# interface_spellman_detector.net
KiCad netlist of a schematic drawn in EAGLE
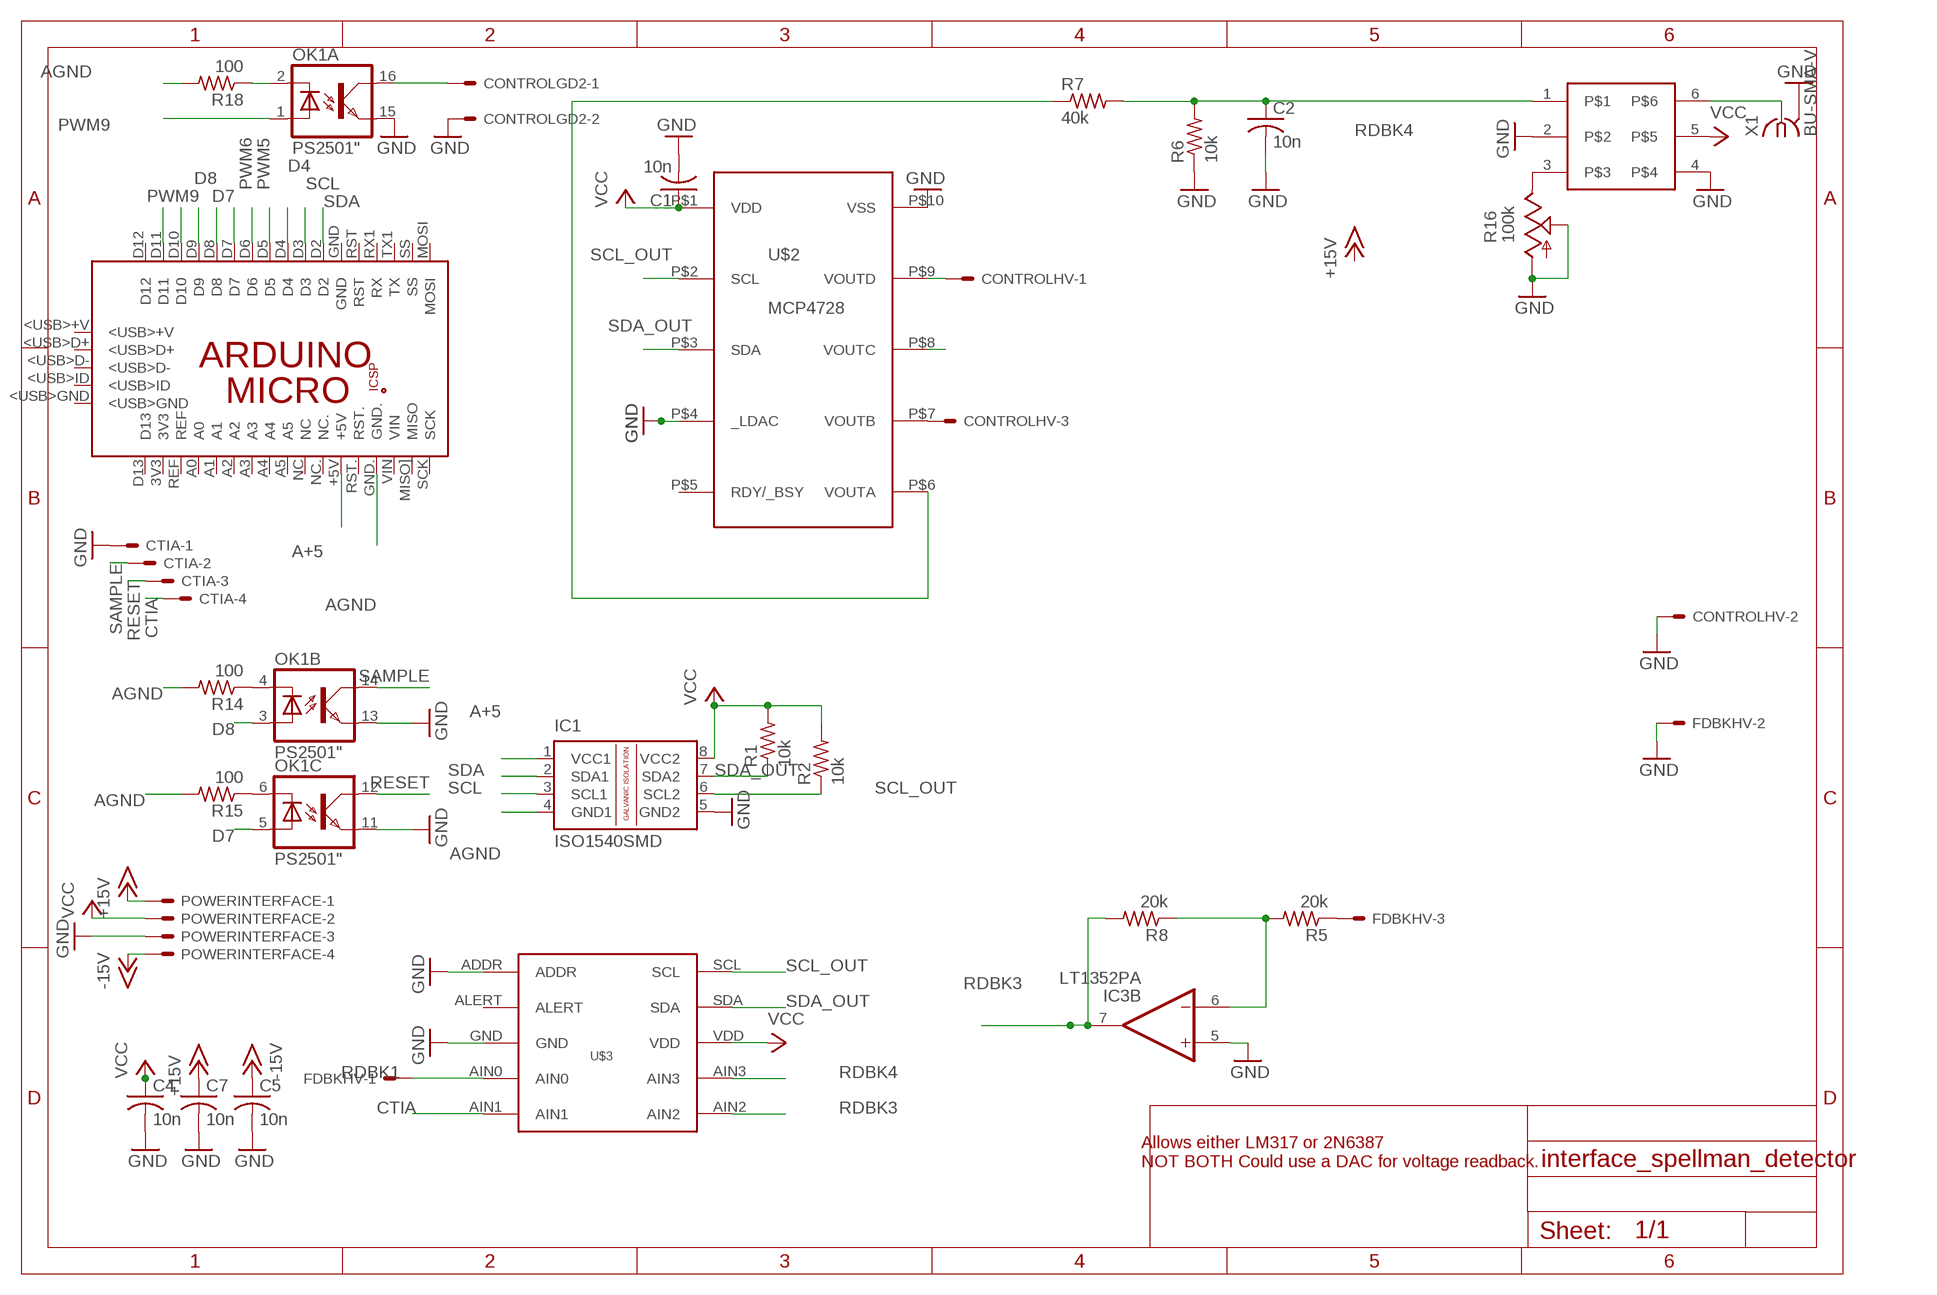
[diagram p0: schematic, sheet 1]

(export (version "E")
  (design (tool "Eeschema 10.0.6"))
  (components
    (comp (ref "C1")
      (value "10n")
      (footprint "eagle-import:C0805K")
      (libsource (lib "eagle-import") (part "C-USC0805K"))
    )
    (comp (ref "C2")
      (value "10n")
      (footprint "eagle-import:C0805K")
      (libsource (lib "eagle-import") (part "resistor_C-USC0805K"))
    )
    (comp (ref "C4")
      (value "10n")
      (footprint "eagle-import:C0805K")
      (libsource (lib "eagle-import") (part "resistor_C-USC0805K"))
    )
    (comp (ref "C5")
      (value "10n")
      (footprint "eagle-import:C0805K")
      (libsource (lib "eagle-import") (part "resistor_C-USC0805K"))
    )
    (comp (ref "C7")
      (value "10n")
      (footprint "eagle-import:C0805K")
      (libsource (lib "eagle-import") (part "resistor_C-USC0805K"))
    )
    (comp (ref "CONTROLGD2")
      (value "KK-156-2")
      (footprint "eagle-import:KK-156-2")
      (libsource (lib "eagle-import") (part "KK-156-2"))
    )
    (comp (ref "CONTROLHV")
      (value "KK-156-3")
      (footprint "eagle-import:KK-156-3")
      (libsource (lib "eagle-import") (part "KK-156-3"))
    )
    (comp (ref "CTIA")
      (value "KK-156-4")
      (footprint "eagle-import:KK-156-4")
      (libsource (lib "eagle-import") (part "KK-156-4"))
    )
    (comp (ref "FDBKHV")
      (value "KK-156-3")
      (footprint "eagle-import:KK-156-3")
      (libsource (lib "eagle-import") (part "KK-156-3"))
    )
    (comp (ref "IC1")
      (value "ISO1540SMD")
      (footprint "eagle-import:SOIC8")
      (libsource (lib "eagle-import") (part "ISO1540SMD"))
    )
    (comp (ref "IC3")
      (value "LT1352PA")
      (footprint "eagle-import:DIL08")
      (libsource (lib "eagle-import") (part "LT1352PA"))
    )
    (comp (ref "OK1")
      (value "PS2501\"")
      (footprint "eagle-import:DIL16")
      (libsource (lib "eagle-import") (part "PS2501{dblquote}"))
    )
    (comp (ref "PCB1")
      (value "ARDUINO_MICRO")
      (footprint "eagle-import:ARDUINO_MICRO")
      (libsource (lib "eagle-import") (part "ARDUINO_MICRO"))
    )
    (comp (ref "POWERINTERFACE")
      (value "KK-156-4")
      (footprint "eagle-import:KK-156-4")
      (libsource (lib "eagle-import") (part "KK-156-4"))
    )
    (comp (ref "R1")
      (value "10k")
      (footprint "eagle-import:R0805")
      (libsource (lib "eagle-import") (part "resistor_R-US_R0805"))
    )
    (comp (ref "R2")
      (value "10k")
      (footprint "eagle-import:R0805")
      (libsource (lib "eagle-import") (part "resistor_R-US_R0805"))
    )
    (comp (ref "R5")
      (value "20k")
      (footprint "eagle-import:R0805")
      (libsource (lib "eagle-import") (part "resistor_R-US_R0805"))
    )
    (comp (ref "R6")
      (value "10k")
      (footprint "eagle-import:R0805")
      (libsource (lib "eagle-import") (part "resistor_R-US_R0805"))
    )
    (comp (ref "R7")
      (value "40k")
      (footprint "eagle-import:R0805")
      (libsource (lib "eagle-import") (part "resistor_R-US_R0805"))
    )
    (comp (ref "R8")
      (value "20k")
      (footprint "eagle-import:R0805")
      (libsource (lib "eagle-import") (part "resistor_R-US_R0805"))
    )
    (comp (ref "R14")
      (value "100")
      (footprint "eagle-import:R0805")
      (libsource (lib "eagle-import") (part "R-US_R0805"))
    )
    (comp (ref "R15")
      (value "100")
      (footprint "eagle-import:R0805")
      (libsource (lib "eagle-import") (part "R-US_R0805"))
    )
    (comp (ref "R16")
      (value "100k")
      (footprint "eagle-import:B64Y")
      (libsource (lib "eagle-import") (part "TRIM_US-B64Y"))
    )
    (comp (ref "R18")
      (value "100")
      (footprint "eagle-import:R0805")
      (libsource (lib "eagle-import") (part "R-US_R0805"))
    )
    (comp (ref "U$1")
      (value "LTC6992SMD")
      (footprint "eagle-import:SOT23-6")
      (libsource (lib "eagle-import") (part "LTC6992SMD"))
    )
    (comp (ref "U$2")
      (value "MCP4728")
      (footprint "eagle-import:MSOP-10")
      (libsource (lib "eagle-import") (part "MCP4728"))
    )
    (comp (ref "U$3")
      (value "ADS1015")
      (footprint "eagle-import:VSOP-10")
      (libsource (lib "eagle-import") (part "ADS1015"))
    )
    (comp (ref "X1")
      (value "BU-SMA-V")
      (footprint "eagle-import:BU-SMA-V")
      (libsource (lib "eagle-import") (part "BU-SMA-V"))
    )
  )
  (nets
    (net (code "1") (name "+15V") (class "Default")
      (node (ref "C7") (pin "1") (pinfunction "1_1") (pintype "passive"))
      (node (ref "POWERINTERFACE") (pin "1") (pinfunction "S_1") (pintype "passive"))
    )
    (net (code "2") (name "-15V") (class "Default")
      (node (ref "C5") (pin "1") (pinfunction "1_1") (pintype "passive"))
      (node (ref "POWERINTERFACE") (pin "4") (pinfunction "S_4") (pintype "passive"))
    )
    (net (code "3") (name "/A+5") (class "Default")
      (node (ref "IC1") (pin "1") (pinfunction "VCC1_1") (pintype "input"))
      (node (ref "PCB1") (pin "+5V") (pinfunction "+5V_+5V") (pintype "bidirectional"))
    )
    (net (code "4") (name "/AGND") (class "Default")
      (node (ref "IC1") (pin "4") (pinfunction "GND1_4") (pintype "input"))
      (node (ref "PCB1") (pin "GND.") (pinfunction "GND._GND.") (pintype "bidirectional"))
      (node (ref "R14") (pin "2") (pinfunction "2_2") (pintype "passive"))
      (node (ref "R15") (pin "2") (pinfunction "2_2") (pintype "passive"))
      (node (ref "R18") (pin "2") (pinfunction "2_2") (pintype "passive"))
    )
    (net (code "5") (name "/CTIA") (class "Default")
      (node (ref "CTIA") (pin "4") (pinfunction "S_4") (pintype "passive"))
      (node (ref "U$3") (pin "AIN1") (pinfunction "AIN1_AIN1") (pintype "bidirectional"))
    )
    (net (code "6") (name "/D4") (class "Default")
      (node (ref "PCB1") (pin "D4") (pinfunction "D4_D4") (pintype "bidirectional"))
    )
    (net (code "7") (name "/D7") (class "Default")
      (node (ref "OK1") (pin "5") (pinfunction "A_5") (pintype "passive"))
      (node (ref "PCB1") (pin "D7") (pinfunction "D7_D7") (pintype "bidirectional"))
    )
    (net (code "8") (name "/D8") (class "Default")
      (node (ref "OK1") (pin "3") (pinfunction "A_3") (pintype "passive"))
      (node (ref "PCB1") (pin "D8") (pinfunction "D8_D8") (pintype "bidirectional"))
    )
    (net (code "9") (name "/PWM5") (class "Default")
      (node (ref "PCB1") (pin "D5") (pinfunction "D5_D5") (pintype "bidirectional"))
    )
    (net (code "10") (name "/PWM6") (class "Default")
      (node (ref "PCB1") (pin "D6") (pinfunction "D6_D6") (pintype "bidirectional"))
    )
    (net (code "11") (name "/PWM9") (class "Default")
      (node (ref "OK1") (pin "1") (pinfunction "A_1") (pintype "passive"))
      (node (ref "PCB1") (pin "D9") (pinfunction "D9_D9") (pintype "bidirectional"))
    )
    (net (code "12") (name "/RDBK1") (class "Default")
      (node (ref "FDBKHV") (pin "1") (pinfunction "S_1") (pintype "passive"))
      (node (ref "U$3") (pin "AIN0") (pinfunction "AIN0_AIN0") (pintype "bidirectional"))
    )
    (net (code "13") (name "/RDBK3") (class "Default")
      (node (ref "IC3") (pin "7") (pinfunction "OUT_7") (pintype "output"))
      (node (ref "R8") (pin "2") (pinfunction "2_2") (pintype "passive"))
      (node (ref "U$3") (pin "AIN2") (pinfunction "AIN2_AIN2") (pintype "bidirectional"))
    )
    (net (code "14") (name "/RDBK4") (class "Default")
      (node (ref "C2") (pin "1") (pinfunction "1_1") (pintype "passive"))
      (node (ref "R6") (pin "2") (pinfunction "2_2") (pintype "passive"))
      (node (ref "R7") (pin "2") (pinfunction "2_2") (pintype "passive"))
      (node (ref "U$1") (pin "1") (pinfunction "P$1_1") (pintype "bidirectional"))
      (node (ref "U$3") (pin "AIN3") (pinfunction "AIN3_AIN3") (pintype "bidirectional"))
    )
    (net (code "15") (name "/RESET") (class "Default")
      (node (ref "CTIA") (pin "3") (pinfunction "S_3") (pintype "passive"))
      (node (ref "OK1") (pin "12") (pinfunction "COL_12") (pintype "passive"))
    )
    (net (code "16") (name "/SAMPLE") (class "Default")
      (node (ref "CTIA") (pin "2") (pinfunction "S_2") (pintype "passive"))
      (node (ref "OK1") (pin "14") (pinfunction "COL_14") (pintype "passive"))
    )
    (net (code "17") (name "/SCL") (class "Default")
      (node (ref "IC1") (pin "3") (pinfunction "SCL1_3") (pintype "input"))
      (node (ref "PCB1") (pin "D3") (pinfunction "D3_D3") (pintype "bidirectional"))
    )
    (net (code "18") (name "/SCL_OUT") (class "Default")
      (node (ref "IC1") (pin "6") (pinfunction "SCL2_6") (pintype "input"))
      (node (ref "R2") (pin "1") (pinfunction "1_1") (pintype "passive"))
      (node (ref "U$2") (pin "P$2") (pinfunction "SCL_P$2") (pintype "bidirectional"))
      (node (ref "U$3") (pin "SCL") (pinfunction "SCL_SCL") (pintype "bidirectional"))
    )
    (net (code "19") (name "/SDA") (class "Default")
      (node (ref "IC1") (pin "2") (pinfunction "SDA1_2") (pintype "input"))
      (node (ref "PCB1") (pin "D2") (pinfunction "D2_D2") (pintype "bidirectional"))
    )
    (net (code "20") (name "/SDA_OUT") (class "Default")
      (node (ref "IC1") (pin "7") (pinfunction "SDA2_7") (pintype "input"))
      (node (ref "R1") (pin "1") (pinfunction "1_1") (pintype "passive"))
      (node (ref "U$2") (pin "P$3") (pinfunction "SDA_P$3") (pintype "bidirectional"))
      (node (ref "U$3") (pin "SDA") (pinfunction "SDA_SDA") (pintype "bidirectional"))
    )
    (net (code "21") (name "GND") (class "Default")
      (node (ref "C1") (pin "2") (pinfunction "2_2") (pintype "passive"))
      (node (ref "C2") (pin "2") (pinfunction "2_2") (pintype "passive"))
      (node (ref "C4") (pin "2") (pinfunction "2_2") (pintype "passive"))
      (node (ref "C5") (pin "2") (pinfunction "2_2") (pintype "passive"))
      (node (ref "C7") (pin "2") (pinfunction "2_2") (pintype "passive"))
      (node (ref "CONTROLGD2") (pin "2") (pinfunction "S_2") (pintype "passive"))
      (node (ref "CONTROLHV") (pin "2") (pinfunction "S_2") (pintype "passive"))
      (node (ref "CTIA") (pin "1") (pinfunction "S_1") (pintype "passive"))
      (node (ref "FDBKHV") (pin "2") (pinfunction "S_2") (pintype "passive"))
      (node (ref "IC1") (pin "5") (pinfunction "GND2_5") (pintype "input"))
      (node (ref "IC3") (pin "5") (pinfunction "+IN_5") (pintype "input"))
      (node (ref "OK1") (pin "11") (pinfunction "EMI_11") (pintype "passive"))
      (node (ref "OK1") (pin "13") (pinfunction "EMI_13") (pintype "passive"))
      (node (ref "OK1") (pin "15") (pinfunction "EMI_15") (pintype "passive"))
      (node (ref "POWERINTERFACE") (pin "3") (pinfunction "S_3") (pintype "passive"))
      (node (ref "R16") (pin "A") (pinfunction "A_A") (pintype "passive"))
      (node (ref "R16") (pin "S") (pinfunction "S_S") (pintype "passive"))
      (node (ref "R6") (pin "1") (pinfunction "1_1") (pintype "passive"))
      (node (ref "U$1") (pin "2") (pinfunction "P$2_2") (pintype "bidirectional"))
      (node (ref "U$1") (pin "4") (pinfunction "P$4_4") (pintype "bidirectional"))
      (node (ref "U$2") (pin "P$10") (pinfunction "VSS_P$10") (pintype "bidirectional"))
      (node (ref "U$2") (pin "P$4") (pinfunction "_LDAC_P$4") (pintype "bidirectional"))
      (node (ref "U$3") (pin "ADDR") (pinfunction "ADDR_ADDR") (pintype "bidirectional"))
      (node (ref "U$3") (pin "GND") (pinfunction "GND_GND") (pintype "bidirectional"))
      (node (ref "X1") (pin "2") (pinfunction "2_2") (pintype "passive"))
      (node (ref "X1") (pin "3") (pinfunction "2_3") (pintype "passive"))
      (node (ref "X1") (pin "4") (pinfunction "2_4") (pintype "passive"))
      (node (ref "X1") (pin "5") (pinfunction "2_5") (pintype "passive"))
    )
    (net (code "22") (name "Net-(CONTROLGD2A-S)") (class "Default")
      (node (ref "CONTROLGD2") (pin "1") (pinfunction "S_1") (pintype "passive"))
      (node (ref "OK1") (pin "16") (pinfunction "COL_16") (pintype "passive"))
    )
    (net (code "23") (name "Net-(CONTROLHVA-S)") (class "Default")
      (node (ref "CONTROLHV") (pin "1") (pinfunction "S_1") (pintype "passive"))
      (node (ref "U$2") (pin "P$9") (pinfunction "VOUTD_P$9") (pintype "bidirectional"))
    )
    (net (code "24") (name "Net-(CONTROLHVC-S)") (class "Default")
      (node (ref "CONTROLHV") (pin "3") (pinfunction "S_3") (pintype "passive"))
      (node (ref "U$2") (pin "P$7") (pinfunction "VOUTB_P$7") (pintype "bidirectional"))
    )
    (net (code "25") (name "Net-(FDBKHVC-S)") (class "Default")
      (node (ref "FDBKHV") (pin "3") (pinfunction "S_3") (pintype "passive"))
      (node (ref "R5") (pin "1") (pinfunction "1_1") (pintype "passive"))
    )
    (net (code "26") (name "Net-(IC3B--IN)") (class "Default")
      (node (ref "IC3") (pin "6") (pinfunction "-IN_6") (pintype "input"))
      (node (ref "R5") (pin "2") (pinfunction "2_2") (pintype "passive"))
      (node (ref "R8") (pin "1") (pinfunction "1_1") (pintype "passive"))
    )
    (net (code "27") (name "Net-(OK1A-C)") (class "Default")
      (node (ref "OK1") (pin "2") (pinfunction "C_2") (pintype "passive"))
      (node (ref "R18") (pin "1") (pinfunction "1_1") (pintype "passive"))
    )
    (net (code "28") (name "Net-(OK1B-C)") (class "Default")
      (node (ref "OK1") (pin "4") (pinfunction "C_4") (pintype "passive"))
      (node (ref "R14") (pin "1") (pinfunction "1_1") (pintype "passive"))
    )
    (net (code "29") (name "Net-(OK1C-C)") (class "Default")
      (node (ref "OK1") (pin "6") (pinfunction "C_6") (pintype "passive"))
      (node (ref "R15") (pin "1") (pinfunction "1_1") (pintype "passive"))
    )
    (net (code "30") (name "Net-(U$1-P$3)") (class "Default")
      (node (ref "R16") (pin "E") (pinfunction "E_E") (pintype "passive"))
      (node (ref "U$1") (pin "3") (pinfunction "P$3_3") (pintype "bidirectional"))
    )
    (net (code "31") (name "Net-(U$1-P$6)") (class "Default")
      (node (ref "U$1") (pin "6") (pinfunction "P$6_6") (pintype "bidirectional"))
      (node (ref "X1") (pin "1") (pinfunction "1_1") (pintype "passive"))
    )
    (net (code "32") (name "Net-(U$2-VOUTA)") (class "Default")
      (node (ref "R7") (pin "1") (pinfunction "1_1") (pintype "passive"))
      (node (ref "U$2") (pin "P$6") (pinfunction "VOUTA_P$6") (pintype "bidirectional"))
    )
    (net (code "33") (name "VCC") (class "Default")
      (node (ref "C1") (pin "1") (pinfunction "1_1") (pintype "passive"))
      (node (ref "C4") (pin "1") (pinfunction "1_1") (pintype "passive"))
      (node (ref "IC1") (pin "8") (pinfunction "VCC2_8") (pintype "input"))
      (node (ref "POWERINTERFACE") (pin "2") (pinfunction "S_2") (pintype "passive"))
      (node (ref "R1") (pin "2") (pinfunction "2_2") (pintype "passive"))
      (node (ref "R2") (pin "2") (pinfunction "2_2") (pintype "passive"))
      (node (ref "U$1") (pin "5") (pinfunction "P$5_5") (pintype "bidirectional"))
      (node (ref "U$2") (pin "P$1") (pinfunction "VDD_P$1") (pintype "bidirectional"))
      (node (ref "U$3") (pin "VDD") (pinfunction "VDD_VDD") (pintype "bidirectional"))
    )
    (net (code "34") (name "unconnected-(PCB1-MISO-PadMISO])") (class "Default")
      (node (ref "PCB1") (pin "MISO]") (pinfunction "MISO_MISO]") (pintype "bidirectional"))
    )
    (net (code "35") (name "unconnected-(PCB1-Pad3V3)") (class "Default")
      (node (ref "PCB1") (pin "3V3") (pinfunction "3V3_3V3") (pintype "bidirectional"))
    )
    (net (code "36") (name "unconnected-(PCB1-Pad5V)") (class "Default")
      (node (ref "PCB1") (pin "5V") (pinfunction "5V_5V") (pintype "bidirectional"))
    )
    (net (code "37") (name "unconnected-(PCB1-Pad<USB>+V)") (class "Default")
      (node (ref "PCB1") (pin "<USB>+V") (pinfunction "<USB>+V_<USB>+V") (pintype "bidirectional"))
    )
    (net (code "38") (name "unconnected-(PCB1-Pad<USB>D+)") (class "Default")
      (node (ref "PCB1") (pin "<USB>D+") (pinfunction "<USB>D+_<USB>D+") (pintype "bidirectional"))
    )
    (net (code "39") (name "unconnected-(PCB1-Pad<USB>D-)") (class "Default")
      (node (ref "PCB1") (pin "<USB>D-") (pinfunction "<USB>D-_<USB>D-") (pintype "bidirectional"))
    )
    (net (code "40") (name "unconnected-(PCB1-Pad<USB>GND)") (class "Default")
      (node (ref "PCB1") (pin "<USB>GND") (pinfunction "<USB>GND_<USB>GND") (pintype "bidirectional"))
    )
    (net (code "41") (name "unconnected-(PCB1-Pad<USB>ID)") (class "Default")
      (node (ref "PCB1") (pin "<USB>ID") (pinfunction "<USB>ID_<USB>ID") (pintype "bidirectional"))
    )
    (net (code "42") (name "unconnected-(PCB1-PadA0)") (class "Default")
      (node (ref "PCB1") (pin "A0") (pinfunction "A0_A0") (pintype "bidirectional"))
    )
    (net (code "43") (name "unconnected-(PCB1-PadA1)") (class "Default")
      (node (ref "PCB1") (pin "A1") (pinfunction "A1_A1") (pintype "bidirectional"))
    )
    (net (code "44") (name "unconnected-(PCB1-PadA2)") (class "Default")
      (node (ref "PCB1") (pin "A2") (pinfunction "A2_A2") (pintype "bidirectional"))
    )
    (net (code "45") (name "unconnected-(PCB1-PadA3)") (class "Default")
      (node (ref "PCB1") (pin "A3") (pinfunction "A3_A3") (pintype "bidirectional"))
    )
    (net (code "46") (name "unconnected-(PCB1-PadA4)") (class "Default")
      (node (ref "PCB1") (pin "A4") (pinfunction "A4_A4") (pintype "bidirectional"))
    )
    (net (code "47") (name "unconnected-(PCB1-PadA5)") (class "Default")
      (node (ref "PCB1") (pin "A5") (pinfunction "A5_A5") (pintype "bidirectional"))
    )
    (net (code "48") (name "unconnected-(PCB1-PadD10)") (class "Default")
      (node (ref "PCB1") (pin "D10") (pinfunction "D10_D10") (pintype "bidirectional"))
    )
    (net (code "49") (name "unconnected-(PCB1-PadD11)") (class "Default")
      (node (ref "PCB1") (pin "D11") (pinfunction "D11_D11") (pintype "bidirectional"))
    )
    (net (code "50") (name "unconnected-(PCB1-PadD12)") (class "Default")
      (node (ref "PCB1") (pin "D12") (pinfunction "D12_D12") (pintype "bidirectional"))
    )
    (net (code "51") (name "unconnected-(PCB1-PadD13)") (class "Default")
      (node (ref "PCB1") (pin "D13") (pinfunction "D13_D13") (pintype "bidirectional"))
    )
    (net (code "52") (name "unconnected-(PCB1-PadGND)") (class "Default")
      (node (ref "PCB1") (pin "GND") (pinfunction "GND_GND") (pintype "bidirectional"))
    )
    (net (code "53") (name "unconnected-(PCB1-PadGND_)") (class "Default")
      (node (ref "PCB1") (pin "GND_") (pinfunction "GND__GND_") (pintype "bidirectional"))
    )
    (net (code "54") (name "unconnected-(PCB1-PadMISO.)") (class "Default")
      (node (ref "PCB1") (pin "MISO.") (pinfunction "MISO._MISO.") (pintype "bidirectional"))
    )
    (net (code "55") (name "unconnected-(PCB1-PadMOSI)") (class "Default")
      (node (ref "PCB1") (pin "MOSI") (pinfunction "MOSI_MOSI") (pintype "bidirectional"))
    )
    (net (code "56") (name "unconnected-(PCB1-PadMOSI.)") (class "Default")
      (node (ref "PCB1") (pin "MOSI.") (pinfunction "MOSI._MOSI.") (pintype "bidirectional"))
    )
    (net (code "57") (name "unconnected-(PCB1-PadNC)") (class "Default")
      (node (ref "PCB1") (pin "NC") (pinfunction "NC_NC") (pintype "bidirectional"))
    )
    (net (code "58") (name "unconnected-(PCB1-PadNC.)") (class "Default")
      (node (ref "PCB1") (pin "NC.") (pinfunction "NC._NC.") (pintype "bidirectional"))
    )
    (net (code "59") (name "unconnected-(PCB1-PadREF)") (class "Default")
      (node (ref "PCB1") (pin "REF") (pinfunction "REF_REF") (pintype "bidirectional"))
    )
    (net (code "60") (name "unconnected-(PCB1-PadRESET..)") (class "Default")
      (node (ref "PCB1") (pin "RESET..") (pinfunction "RESET.._RESET..") (pintype "bidirectional"))
    )
    (net (code "61") (name "unconnected-(PCB1-PadRST)") (class "Default")
      (node (ref "PCB1") (pin "RST") (pinfunction "RST_RST") (pintype "bidirectional"))
    )
    (net (code "62") (name "unconnected-(PCB1-PadRST.)") (class "Default")
      (node (ref "PCB1") (pin "RST.") (pinfunction "RST._RST.") (pintype "bidirectional"))
    )
    (net (code "63") (name "unconnected-(PCB1-PadSCK)") (class "Default")
      (node (ref "PCB1") (pin "SCK") (pinfunction "SCK_SCK") (pintype "bidirectional"))
    )
    (net (code "64") (name "unconnected-(PCB1-PadSCK.)") (class "Default")
      (node (ref "PCB1") (pin "SCK.") (pinfunction "SCK._SCK.") (pintype "bidirectional"))
    )
    (net (code "65") (name "unconnected-(PCB1-PadSS)") (class "Default")
      (node (ref "PCB1") (pin "SS") (pinfunction "SS_SS") (pintype "bidirectional"))
    )
    (net (code "66") (name "unconnected-(PCB1-PadVIN)") (class "Default")
      (node (ref "PCB1") (pin "VIN") (pinfunction "VIN_VIN") (pintype "bidirectional"))
    )
    (net (code "67") (name "unconnected-(PCB1-RX-PadRX1)") (class "Default")
      (node (ref "PCB1") (pin "RX1") (pinfunction "RX_RX1") (pintype "bidirectional"))
    )
    (net (code "68") (name "unconnected-(PCB1-TX-PadTX1)") (class "Default")
      (node (ref "PCB1") (pin "TX1") (pinfunction "TX_TX1") (pintype "bidirectional"))
    )
    (net (code "69") (name "unconnected-(U$2-RDY{slash}_BSY-PadP$5)") (class "Default")
      (node (ref "U$2") (pin "P$5") (pinfunction "RDY/_BSY_P$5") (pintype "bidirectional"))
    )
    (net (code "70") (name "unconnected-(U$2-VOUTC-PadP$8)") (class "Default")
      (node (ref "U$2") (pin "P$8") (pinfunction "VOUTC_P$8") (pintype "bidirectional"))
    )
    (net (code "71") (name "unconnected-(U$3-PadALERT)") (class "Default")
      (node (ref "U$3") (pin "ALERT") (pinfunction "ALERT_ALERT") (pintype "bidirectional"))
    )
  )
)
